# STE2007_Nokia_1202.net
KiCad netlist of a schematic drawn in Altium Designer
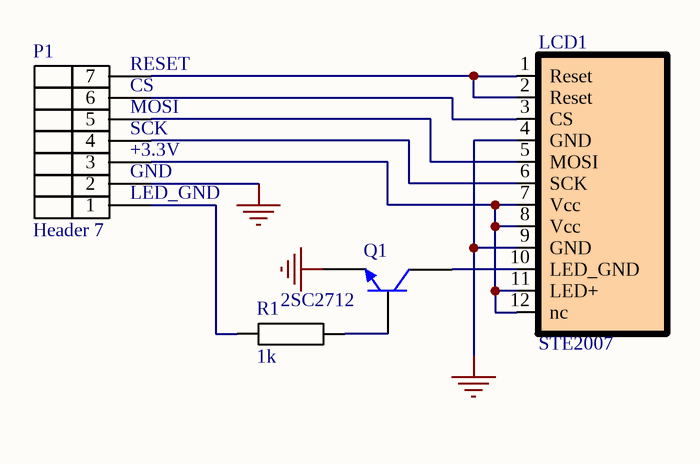
[diagram p0: STE2007_Nokia 1202.SchDoc]

(export (version "E")
  (design (tool "Eeschema 10.0.6"))
  (components
    (comp (ref "LCD1")
      (value "STE2007")
      (footprint "STE2007_Nokia 1202:Display_Nokia 1202")
      (libsource (lib "STE2007_Nokia 1202") (part "Display_Nokia 1202"))
    )
    (comp (ref "P1")
      (value "Header 7")
      (footprint "Пять разрядов:HDR1X7")
      (description "Header, 7-Pin")
      (fields (field (name "PUBLISHER") "Altium Limited"))
      (libsource (lib "PCB_Project_1") (part "Header 7"))
    )
    (comp (ref "Q1")
      (value "2SC2712")
      (footprint "SOT23_N")
      (description "NPN")
      (libsource (lib "PCB_Project_1") (part "2SC2712"))
    )
    (comp (ref "R1") (value "1k") (footprint "6-0805_N") (libsource (lib "PCB_Project_1") (part "1k")))
  )
  (nets
    (net (code "1") (name "GND") (class "Default")
      (node (ref "LCD1") (pin "4") (pinfunction "GND_4") (pintype "passive"))
      (node (ref "LCD1") (pin "9") (pinfunction "GND_9") (pintype "passive"))
      (node (ref "P1") (pin "2") (pinfunction "2_2") (pintype "passive"))
      (node (ref "Q1") (pin "2") (pinfunction "E_2") (pintype "passive"))
    )
    (net (code "2") (name "Net-(LCD1-CS)") (class "Default")
      (node (ref "LCD1") (pin "3") (pinfunction "CS_3") (pintype "passive"))
      (node (ref "P1") (pin "6") (pinfunction "6_6") (pintype "passive"))
    )
    (net (code "3") (name "Net-(LCD1-LED+)") (class "Default")
      (node (ref "LCD1") (pin "11") (pinfunction "LED+_11") (pintype "passive"))
      (node (ref "LCD1") (pin "12") (pinfunction "nc_12") (pintype "passive"))
      (node (ref "LCD1") (pin "7") (pinfunction "Vcc_7") (pintype "passive"))
      (node (ref "LCD1") (pin "8") (pinfunction "Vcc_8") (pintype "passive"))
      (node (ref "P1") (pin "3") (pinfunction "3_3") (pintype "passive"))
    )
    (net (code "4") (name "Net-(LCD1-LED_GND)") (class "Default")
      (node (ref "LCD1") (pin "10") (pinfunction "LED_GND_10") (pintype "passive"))
      (node (ref "Q1") (pin "3") (pinfunction "C_3") (pintype "passive"))
    )
    (net (code "5") (name "Net-(LCD1-MOSI)") (class "Default")
      (node (ref "LCD1") (pin "5") (pinfunction "MOSI_5") (pintype "passive"))
      (node (ref "P1") (pin "5") (pinfunction "5_5") (pintype "passive"))
    )
    (net (code "6") (name "Net-(LCD1-Reset-Pad1)") (class "Default")
      (node (ref "LCD1") (pin "1") (pinfunction "Reset_1") (pintype "passive"))
      (node (ref "LCD1") (pin "2") (pinfunction "Reset_2") (pintype "passive"))
      (node (ref "P1") (pin "7") (pinfunction "7_7") (pintype "passive"))
    )
    (net (code "7") (name "Net-(LCD1-SCK)") (class "Default")
      (node (ref "LCD1") (pin "6") (pinfunction "SCK_6") (pintype "passive"))
      (node (ref "P1") (pin "4") (pinfunction "4_4") (pintype "passive"))
    )
    (net (code "8") (name "Net-(P1-Pad1)") (class "Default")
      (node (ref "P1") (pin "1") (pinfunction "1_1") (pintype "passive"))
      (node (ref "R1") (pin "1") (pinfunction "1_1") (pintype "passive"))
    )
    (net (code "9") (name "Net-(Q1-B)") (class "Default")
      (node (ref "Q1") (pin "1") (pinfunction "B_1") (pintype "passive"))
      (node (ref "R1") (pin "2") (pinfunction "2_2") (pintype "passive"))
    )
  )
)
